# MTX_pic_piggyback.net
KiCad netlist of a schematic drawn in EAGLE
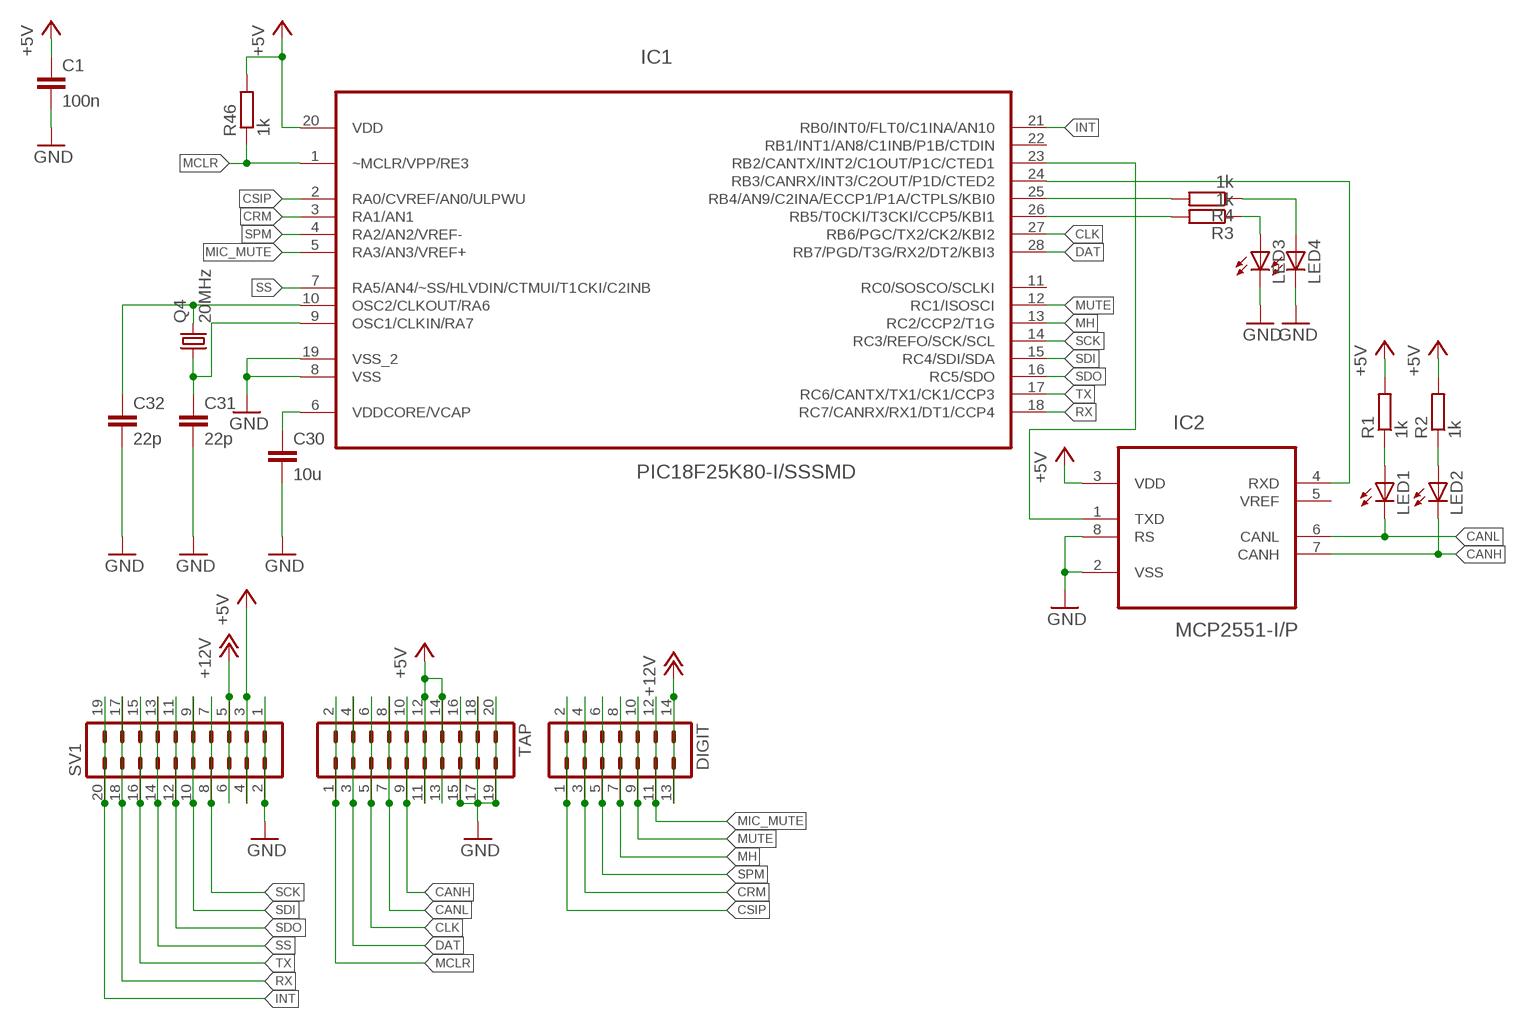
[diagram p0: schematic, sheet 1]

(export (version "E")
  (design (tool "Eeschema 10.0.6"))
  (components
    (comp (ref "C1")
      (value "100n")
      (footprint "eagle-import:C0805")
      (libsource (lib "eagle-import") (part "C-EUC0805"))
    )
    (comp (ref "C30")
      (value "10u")
      (footprint "eagle-import:C0805")
      (libsource (lib "eagle-import") (part "C-EUC0805"))
    )
    (comp (ref "C31")
      (value "22p")
      (footprint "eagle-import:C0805")
      (libsource (lib "eagle-import") (part "C-EUC0805"))
    )
    (comp (ref "C32")
      (value "22p")
      (footprint "eagle-import:C0805")
      (libsource (lib "eagle-import") (part "C-EUC0805"))
    )
    (comp (ref "DIGIT")
      (value "MA07-2")
      (footprint "eagle-import:MA07-2")
      (libsource (lib "eagle-import") (part "MA07-2"))
    )
    (comp (ref "IC1")
      (value "PIC18F25K80-I/SSSMD")
      (footprint "eagle-import:SOP65P780X200-28N")
      (libsource (lib "eagle-import") (part "PIC18F25K80-I/SSSMD"))
    )
    (comp (ref "IC2")
      (value "MCP2551-I/P")
      (footprint "eagle-import:DIP254P762X432-8")
      (libsource (lib "eagle-import") (part "MCP2551-I/P"))
    )
    (comp (ref "LED1")
      (value "LEDCHIP-LED0805")
      (footprint "eagle-import:CHIP-LED0805")
      (libsource (lib "eagle-import") (part "LEDCHIP-LED0805"))
    )
    (comp (ref "LED2")
      (value "LEDCHIP-LED0805")
      (footprint "eagle-import:CHIP-LED0805")
      (libsource (lib "eagle-import") (part "LEDCHIP-LED0805"))
    )
    (comp (ref "LED3")
      (value "LEDCHIP-LED0805")
      (footprint "eagle-import:CHIP-LED0805")
      (libsource (lib "eagle-import") (part "LEDCHIP-LED0805"))
    )
    (comp (ref "LED4")
      (value "LEDCHIP-LED0805")
      (footprint "eagle-import:CHIP-LED0805")
      (libsource (lib "eagle-import") (part "LEDCHIP-LED0805"))
    )
    (comp (ref "Q4")
      (value "20MHz")
      (footprint "eagle-import:HC49UP")
      (libsource (lib "eagle-import") (part "CRYSTALHC49UP"))
    )
    (comp (ref "R1")
      (value "1k")
      (footprint "eagle-import:R0805")
      (libsource (lib "eagle-import") (part "R-EU_R0805"))
    )
    (comp (ref "R2")
      (value "1k")
      (footprint "eagle-import:R0805")
      (libsource (lib "eagle-import") (part "R-EU_R0805"))
    )
    (comp (ref "R3")
      (value "1k")
      (footprint "eagle-import:R0805")
      (libsource (lib "eagle-import") (part "R-EU_R0805"))
    )
    (comp (ref "R4")
      (value "1k")
      (footprint "eagle-import:R0805")
      (libsource (lib "eagle-import") (part "R-EU_R0805"))
    )
    (comp (ref "R46")
      (value "1k")
      (footprint "eagle-import:R0805")
      (libsource (lib "eagle-import") (part "R-EU_R0805"))
    )
    (comp (ref "SV1")
      (value "MA10-2")
      (footprint "eagle-import:MA10-2")
      (libsource (lib "eagle-import") (part "MA10-2"))
    )
    (comp (ref "TAP")
      (value "MA10-2")
      (footprint "eagle-import:MA10-2")
      (libsource (lib "eagle-import") (part "MA10-2"))
    )
  )
  (nets
    (net (code "1") (name "+5V") (class "Default")
      (node (ref "C1") (pin "1") (pinfunction "1_1") (pintype "passive"))
      (node (ref "IC1") (pin "20") (pinfunction "VDD_20") (pintype "power_in"))
      (node (ref "IC2") (pin "3") (pinfunction "VDD_3") (pintype "power_in"))
      (node (ref "R1") (pin "2") (pinfunction "2_2") (pintype "passive"))
      (node (ref "R2") (pin "2") (pinfunction "2_2") (pintype "passive"))
      (node (ref "R46") (pin "2") (pinfunction "2_2") (pintype "passive"))
      (node (ref "SV1") (pin "3") (pinfunction "3_3") (pintype "passive"))
      (node (ref "SV1") (pin "4") (pinfunction "4_4") (pintype "passive"))
      (node (ref "TAP") (pin "11") (pinfunction "11_11") (pintype "passive"))
      (node (ref "TAP") (pin "12") (pinfunction "12_12") (pintype "passive"))
      (node (ref "TAP") (pin "13") (pinfunction "13_13") (pintype "passive"))
      (node (ref "TAP") (pin "14") (pinfunction "14_14") (pintype "passive"))
    )
    (net (code "2") (name "+12V") (class "Default")
      (node (ref "DIGIT") (pin "13") (pinfunction "13_13") (pintype "passive"))
      (node (ref "DIGIT") (pin "14") (pinfunction "14_14") (pintype "passive"))
      (node (ref "SV1") (pin "5") (pinfunction "5_5") (pintype "passive"))
      (node (ref "SV1") (pin "6") (pinfunction "6_6") (pintype "passive"))
    )
    (net (code "3") (name "CANH") (class "Default")
      (node (ref "IC2") (pin "7") (pinfunction "CANH_7") (pintype "bidirectional"))
      (node (ref "LED2") (pin "C") (pinfunction "C_C") (pintype "passive"))
      (node (ref "TAP") (pin "10") (pinfunction "10_10") (pintype "passive"))
      (node (ref "TAP") (pin "9") (pinfunction "9_9") (pintype "passive"))
    )
    (net (code "4") (name "CANL") (class "Default")
      (node (ref "IC2") (pin "6") (pinfunction "CANL_6") (pintype "bidirectional"))
      (node (ref "LED1") (pin "C") (pinfunction "C_C") (pintype "passive"))
      (node (ref "TAP") (pin "7") (pinfunction "7_7") (pintype "passive"))
      (node (ref "TAP") (pin "8") (pinfunction "8_8") (pintype "passive"))
    )
    (net (code "5") (name "CLK") (class "Default")
      (node (ref "IC1") (pin "27") (pinfunction "RB6/PGC/TX2/CK2/KBI2_27") (pintype "bidirectional"))
      (node (ref "TAP") (pin "5") (pinfunction "5_5") (pintype "passive"))
      (node (ref "TAP") (pin "6") (pinfunction "6_6") (pintype "passive"))
    )
    (net (code "6") (name "CRM") (class "Default")
      (node (ref "DIGIT") (pin "3") (pinfunction "3_3") (pintype "passive"))
      (node (ref "DIGIT") (pin "4") (pinfunction "4_4") (pintype "passive"))
      (node (ref "IC1") (pin "3") (pinfunction "RA1/AN1_3") (pintype "bidirectional"))
    )
    (net (code "7") (name "CSIP") (class "Default")
      (node (ref "DIGIT") (pin "1") (pinfunction "1_1") (pintype "passive"))
      (node (ref "DIGIT") (pin "2") (pinfunction "2_2") (pintype "passive"))
      (node (ref "IC1") (pin "2") (pinfunction "RA0/CVREF/AN0/ULPWU_2") (pintype "bidirectional"))
    )
    (net (code "8") (name "DAT") (class "Default")
      (node (ref "IC1") (pin "28") (pinfunction "RB7/PGD/T3G/RX2/DT2/KBI3_28") (pintype "bidirectional"))
      (node (ref "TAP") (pin "3") (pinfunction "3_3") (pintype "passive"))
      (node (ref "TAP") (pin "4") (pinfunction "4_4") (pintype "passive"))
    )
    (net (code "9") (name "GND") (class "Default")
      (node (ref "C1") (pin "2") (pinfunction "2_2") (pintype "passive"))
      (node (ref "C30") (pin "2") (pinfunction "2_2") (pintype "passive"))
      (node (ref "C31") (pin "2") (pinfunction "2_2") (pintype "passive"))
      (node (ref "C32") (pin "2") (pinfunction "2_2") (pintype "passive"))
      (node (ref "IC1") (pin "19") (pinfunction "VSS_2_19") (pintype "power_in"))
      (node (ref "IC1") (pin "8") (pinfunction "VSS_8") (pintype "power_in"))
      (node (ref "IC2") (pin "2") (pinfunction "VSS_2") (pintype "power_in"))
      (node (ref "IC2") (pin "8") (pinfunction "RS_8") (pintype "input"))
      (node (ref "LED3") (pin "C") (pinfunction "C_C") (pintype "passive"))
      (node (ref "LED4") (pin "C") (pinfunction "C_C") (pintype "passive"))
      (node (ref "SV1") (pin "1") (pinfunction "1_1") (pintype "passive"))
      (node (ref "SV1") (pin "2") (pinfunction "2_2") (pintype "passive"))
      (node (ref "TAP") (pin "15") (pinfunction "15_15") (pintype "passive"))
      (node (ref "TAP") (pin "16") (pinfunction "16_16") (pintype "passive"))
      (node (ref "TAP") (pin "17") (pinfunction "17_17") (pintype "passive"))
      (node (ref "TAP") (pin "18") (pinfunction "18_18") (pintype "passive"))
      (node (ref "TAP") (pin "19") (pinfunction "19_19") (pintype "passive"))
      (node (ref "TAP") (pin "20") (pinfunction "20_20") (pintype "passive"))
    )
    (net (code "10") (name "INT") (class "Default")
      (node (ref "IC1") (pin "21") (pinfunction "RB0/INT0/FLT0/C1INA/AN10_21") (pintype "bidirectional"))
      (node (ref "SV1") (pin "19") (pinfunction "19_19") (pintype "passive"))
      (node (ref "SV1") (pin "20") (pinfunction "20_20") (pintype "passive"))
    )
    (net (code "11") (name "MCLR") (class "Default")
      (node (ref "IC1") (pin "1") (pinfunction "~{MCLR/VPP/RE3}_1") (pintype "input"))
      (node (ref "R46") (pin "1") (pinfunction "1_1") (pintype "passive"))
      (node (ref "TAP") (pin "1") (pinfunction "1_1") (pintype "passive"))
      (node (ref "TAP") (pin "2") (pinfunction "2_2") (pintype "passive"))
    )
    (net (code "12") (name "MH") (class "Default")
      (node (ref "DIGIT") (pin "7") (pinfunction "7_7") (pintype "passive"))
      (node (ref "DIGIT") (pin "8") (pinfunction "8_8") (pintype "passive"))
      (node (ref "IC1") (pin "13") (pinfunction "RC2/CCP2/T1G_13") (pintype "bidirectional"))
    )
    (net (code "13") (name "MIC_MUTE") (class "Default")
      (node (ref "DIGIT") (pin "11") (pinfunction "11_11") (pintype "passive"))
      (node (ref "DIGIT") (pin "12") (pinfunction "12_12") (pintype "passive"))
      (node (ref "IC1") (pin "5") (pinfunction "RA3/AN3/VREF+_5") (pintype "bidirectional"))
    )
    (net (code "14") (name "MUTE") (class "Default")
      (node (ref "DIGIT") (pin "10") (pinfunction "10_10") (pintype "passive"))
      (node (ref "DIGIT") (pin "9") (pinfunction "9_9") (pintype "passive"))
      (node (ref "IC1") (pin "12") (pinfunction "RC1/ISOSCI_12") (pintype "bidirectional"))
    )
    (net (code "15") (name "Net-(IC1-OSC1{slash}CLKIN{slash}RA7)") (class "Default")
      (node (ref "C31") (pin "1") (pinfunction "1_1") (pintype "passive"))
      (node (ref "IC1") (pin "9") (pinfunction "OSC1/CLKIN/RA7_9") (pintype "bidirectional"))
      (node (ref "Q4") (pin "1") (pinfunction "1_1") (pintype "passive"))
    )
    (net (code "16") (name "Net-(IC1-OSC2{slash}CLKOUT{slash}RA6)") (class "Default")
      (node (ref "C32") (pin "1") (pinfunction "1_1") (pintype "passive"))
      (node (ref "IC1") (pin "10") (pinfunction "OSC2/CLKOUT/RA6_10") (pintype "bidirectional"))
      (node (ref "Q4") (pin "2") (pinfunction "2_2") (pintype "passive"))
    )
    (net (code "17") (name "Net-(IC1-RB2{slash}CANTX{slash}INT2{slash}C1OUT{slash}P1C{slash}CTED1)") (class "Default")
      (node (ref "IC1") (pin "23") (pinfunction "RB2/CANTX/INT2/C1OUT/P1C/CTED1_23") (pintype "bidirectional"))
      (node (ref "IC2") (pin "1") (pinfunction "TXD_1") (pintype "input"))
    )
    (net (code "18") (name "Net-(IC1-RB3{slash}CANRX{slash}INT3{slash}C2OUT{slash}P1D{slash}CTED2)") (class "Default")
      (node (ref "IC1") (pin "24") (pinfunction "RB3/CANRX/INT3/C2OUT/P1D/CTED2_24") (pintype "bidirectional"))
      (node (ref "IC2") (pin "4") (pinfunction "RXD_4") (pintype "output"))
    )
    (net (code "19") (name "Net-(IC1-RB4{slash}AN9{slash}C2INA{slash}ECCP1{slash}P1A{slash}CTPLS{slash}KBI0)") (class "Default")
      (node (ref "IC1") (pin "25") (pinfunction "RB4/AN9/C2INA/ECCP1/P1A/CTPLS/KBI0_25") (pintype "bidirectional"))
      (node (ref "R4") (pin "2") (pinfunction "2_2") (pintype "passive"))
    )
    (net (code "20") (name "Net-(IC1-RB5{slash}T0CKI{slash}T3CKI{slash}CCP5{slash}KBI1)") (class "Default")
      (node (ref "IC1") (pin "26") (pinfunction "RB5/T0CKI/T3CKI/CCP5/KBI1_26") (pintype "bidirectional"))
      (node (ref "R3") (pin "2") (pinfunction "2_2") (pintype "passive"))
    )
    (net (code "21") (name "Net-(IC1-VDDCORE{slash}VCAP)") (class "Default")
      (node (ref "C30") (pin "1") (pinfunction "1_1") (pintype "passive"))
      (node (ref "IC1") (pin "6") (pinfunction "VDDCORE/VCAP_6") (pintype "bidirectional"))
    )
    (net (code "22") (name "Net-(LED1-PadA)") (class "Default")
      (node (ref "LED1") (pin "A") (pinfunction "A_A") (pintype "passive"))
      (node (ref "R1") (pin "1") (pinfunction "1_1") (pintype "passive"))
    )
    (net (code "23") (name "Net-(LED2-PadA)") (class "Default")
      (node (ref "LED2") (pin "A") (pinfunction "A_A") (pintype "passive"))
      (node (ref "R2") (pin "1") (pinfunction "1_1") (pintype "passive"))
    )
    (net (code "24") (name "Net-(LED3-PadA)") (class "Default")
      (node (ref "LED3") (pin "A") (pinfunction "A_A") (pintype "passive"))
      (node (ref "R3") (pin "1") (pinfunction "1_1") (pintype "passive"))
    )
    (net (code "25") (name "Net-(LED4-PadA)") (class "Default")
      (node (ref "LED4") (pin "A") (pinfunction "A_A") (pintype "passive"))
      (node (ref "R4") (pin "1") (pinfunction "1_1") (pintype "passive"))
    )
    (net (code "26") (name "RX") (class "Default")
      (node (ref "IC1") (pin "18") (pinfunction "RC7/CANRX/RX1/DT1/CCP4_18") (pintype "bidirectional"))
      (node (ref "SV1") (pin "17") (pinfunction "17_17") (pintype "passive"))
      (node (ref "SV1") (pin "18") (pinfunction "18_18") (pintype "passive"))
    )
    (net (code "27") (name "SCK") (class "Default")
      (node (ref "IC1") (pin "14") (pinfunction "RC3/REFO/SCK/SCL_14") (pintype "bidirectional"))
      (node (ref "SV1") (pin "7") (pinfunction "7_7") (pintype "passive"))
      (node (ref "SV1") (pin "8") (pinfunction "8_8") (pintype "passive"))
    )
    (net (code "28") (name "SDI") (class "Default")
      (node (ref "IC1") (pin "15") (pinfunction "RC4/SDI/SDA_15") (pintype "bidirectional"))
      (node (ref "SV1") (pin "10") (pinfunction "10_10") (pintype "passive"))
      (node (ref "SV1") (pin "9") (pinfunction "9_9") (pintype "passive"))
    )
    (net (code "29") (name "SDO") (class "Default")
      (node (ref "IC1") (pin "16") (pinfunction "RC5/SDO_16") (pintype "bidirectional"))
      (node (ref "SV1") (pin "11") (pinfunction "11_11") (pintype "passive"))
      (node (ref "SV1") (pin "12") (pinfunction "12_12") (pintype "passive"))
    )
    (net (code "30") (name "SPM") (class "Default")
      (node (ref "DIGIT") (pin "5") (pinfunction "5_5") (pintype "passive"))
      (node (ref "DIGIT") (pin "6") (pinfunction "6_6") (pintype "passive"))
      (node (ref "IC1") (pin "4") (pinfunction "RA2/AN2/VREF-_4") (pintype "bidirectional"))
    )
    (net (code "31") (name "SS") (class "Default")
      (node (ref "IC1") (pin "7") (pinfunction "RA5/AN4/~{SS/HLVDIN/CTMUI/T1CKI/C2INB}_7") (pintype "bidirectional"))
      (node (ref "SV1") (pin "13") (pinfunction "13_13") (pintype "passive"))
      (node (ref "SV1") (pin "14") (pinfunction "14_14") (pintype "passive"))
    )
    (net (code "32") (name "TX") (class "Default")
      (node (ref "IC1") (pin "17") (pinfunction "RC6/CANTX/TX1/CK1/CCP3_17") (pintype "bidirectional"))
      (node (ref "SV1") (pin "15") (pinfunction "15_15") (pintype "passive"))
      (node (ref "SV1") (pin "16") (pinfunction "16_16") (pintype "passive"))
    )
    (net (code "33") (name "unconnected-(IC1-RB1{slash}INT1{slash}AN8{slash}C1INB{slash}P1B{slash}CTDIN-Pad22)") (class "Default")
      (node (ref "IC1") (pin "22") (pinfunction "RB1/INT1/AN8/C1INB/P1B/CTDIN_22") (pintype "bidirectional"))
    )
    (net (code "34") (name "unconnected-(IC1-RC0{slash}SOSCO{slash}SCLKI-Pad11)") (class "Default")
      (node (ref "IC1") (pin "11") (pinfunction "RC0/SOSCO/SCLKI_11") (pintype "bidirectional"))
    )
    (net (code "35") (name "unconnected-(IC2-VREF-Pad5)") (class "Default")
      (node (ref "IC2") (pin "5") (pinfunction "VREF_5") (pintype "output"))
    )
  )
)
